# Air858.net
KiCad netlist of a schematic drawn in EAGLE
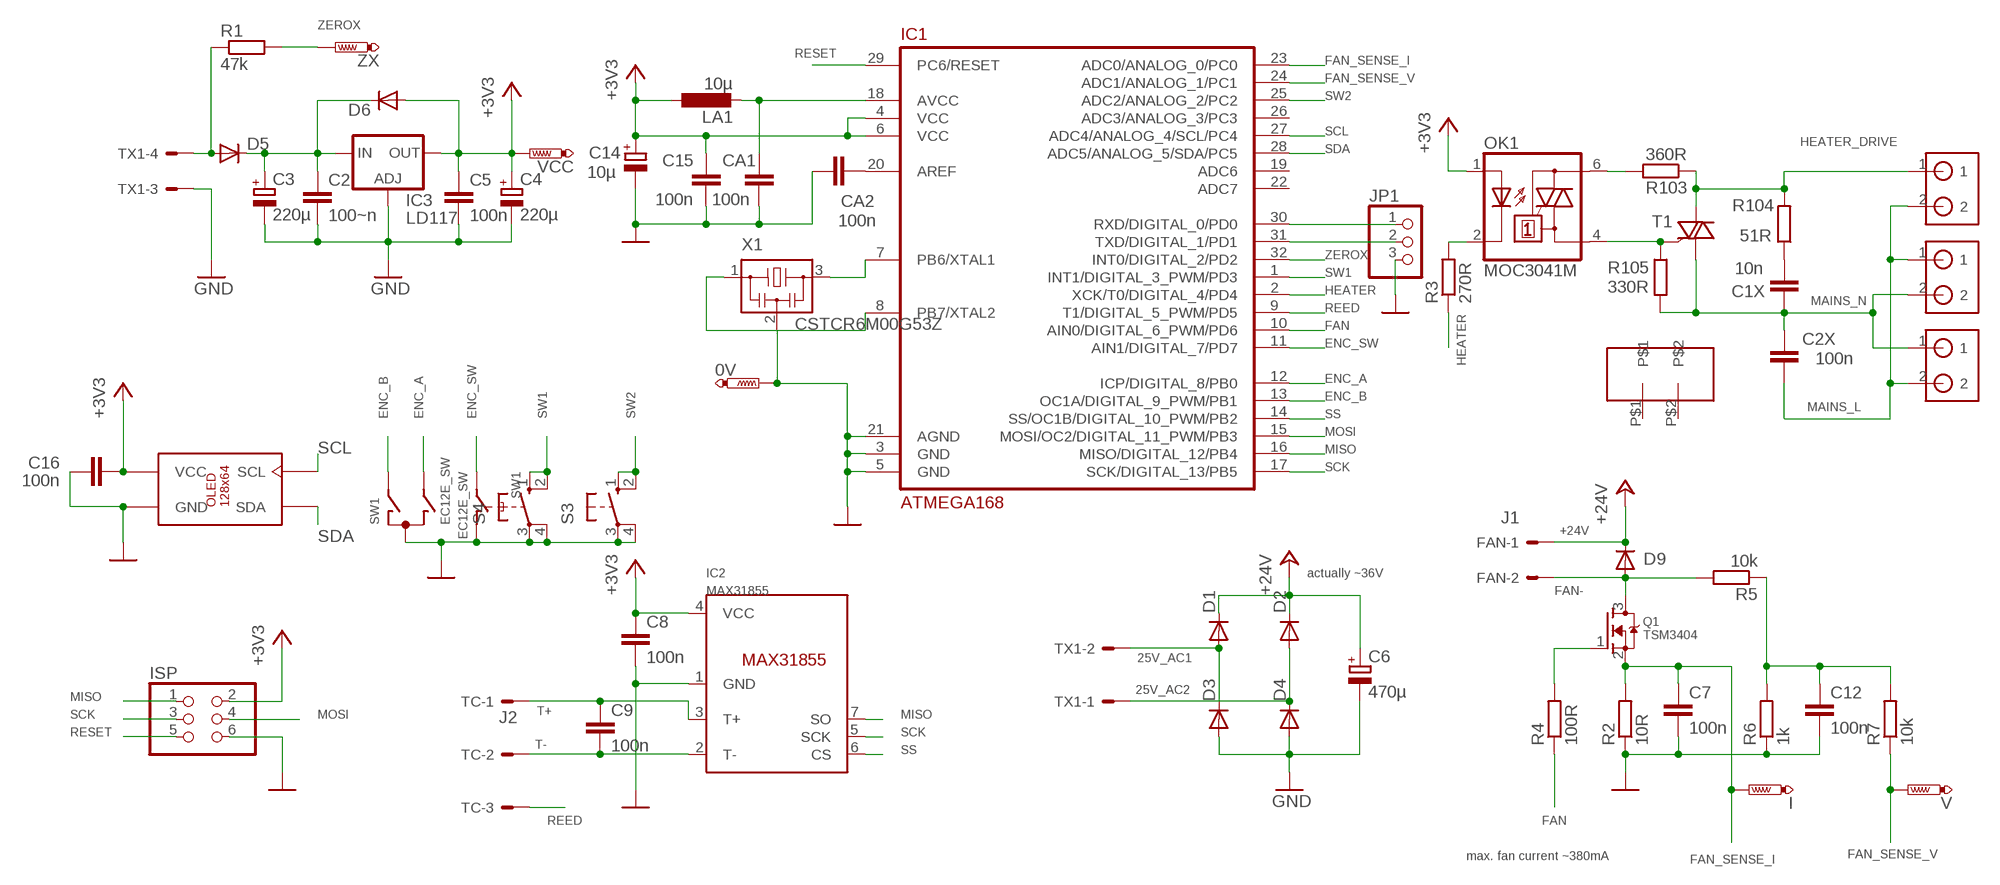
[diagram p0: schematic, sheet 1]

(export (version "E")
  (design (tool "Eeschema 10.0.6"))
  (components
    (comp (ref "0V")
      (value "PTR1B1,27")
      (footprint "eagle-import:B1,27")
      (libsource (lib "eagle-import") (part "PTR1B1,27"))
    )
    (comp (ref "C1X")
      (value "10n")
      (footprint "eagle-import:C075-032X103")
      (libsource (lib "eagle-import") (part "C-EU075-032X103"))
    )
    (comp (ref "C2")
      (value "100~n")
      (footprint "eagle-import:C0603")
      (libsource (lib "eagle-import") (part "C-EUC0603"))
    )
    (comp (ref "C2X")
      (value "100n")
      (footprint "eagle-import:C150-054X183")
      (libsource (lib "eagle-import") (part "C-EU150-054X183"))
    )
    (comp (ref "C3")
      (value "220µ")
      (footprint "eagle-import:SMC_E")
      (libsource (lib "eagle-import") (part "CPOL-EUSMCE"))
    )
    (comp (ref "C4")
      (value "220µ")
      (footprint "eagle-import:SMC_E")
      (libsource (lib "eagle-import") (part "CPOL-EUSMCE"))
    )
    (comp (ref "C5")
      (value "100n")
      (footprint "eagle-import:C0603")
      (libsource (lib "eagle-import") (part "C-EUC0603"))
    )
    (comp (ref "C6")
      (value "470µ")
      (footprint "eagle-import:E5-10,5")
      (libsource (lib "eagle-import") (part "CPOL-EUE5-10.5"))
    )
    (comp (ref "C7")
      (value "100n")
      (footprint "eagle-import:C0603K")
      (libsource (lib "eagle-import") (part "C-EUC0603K"))
    )
    (comp (ref "C8")
      (value "100n")
      (footprint "eagle-import:C0603K")
      (libsource (lib "eagle-import") (part "C-EUC0603K"))
    )
    (comp (ref "C9")
      (value "100n")
      (footprint "eagle-import:C0603K")
      (libsource (lib "eagle-import") (part "C-EUC0603K"))
    )
    (comp (ref "C12")
      (value "100n")
      (footprint "eagle-import:C0603K")
      (libsource (lib "eagle-import") (part "C-EUC0603K"))
    )
    (comp (ref "C14")
      (value "10µ")
      (footprint "eagle-import:B_3528-21W")
      (libsource (lib "eagle-import") (part "CPOL-EUB/3528-21W"))
    )
    (comp (ref "C15")
      (value "100n")
      (footprint "eagle-import:C0603K")
      (libsource (lib "eagle-import") (part "C-EUC0603K"))
    )
    (comp (ref "C16")
      (value "100n")
      (footprint "eagle-import:C0603K")
      (libsource (lib "eagle-import") (part "C-EUC0603K"))
    )
    (comp (ref "CA1")
      (value "100n")
      (footprint "eagle-import:C0603K")
      (libsource (lib "eagle-import") (part "C-EUC0603K"))
    )
    (comp (ref "CA2")
      (value "100n")
      (footprint "eagle-import:C0603K")
      (libsource (lib "eagle-import") (part "C-EUC0603K"))
    )
    (comp (ref "D1")
      (value "DIODE-DO-214AC")
      (footprint "eagle-import:DO-214AC")
      (libsource (lib "eagle-import") (part "DIODE-DO-214AC"))
    )
    (comp (ref "D2")
      (value "DIODE-DO-214AC")
      (footprint "eagle-import:DO-214AC")
      (libsource (lib "eagle-import") (part "DIODE-DO-214AC"))
    )
    (comp (ref "D3")
      (value "DIODE-DO-214AC")
      (footprint "eagle-import:DO-214AC")
      (libsource (lib "eagle-import") (part "DIODE-DO-214AC"))
    )
    (comp (ref "D4")
      (value "DIODE-DO-214AC")
      (footprint "eagle-import:DO-214AC")
      (libsource (lib "eagle-import") (part "DIODE-DO-214AC"))
    )
    (comp (ref "D5")
      (value "DIODE-DO-214AC")
      (footprint "eagle-import:DO-214AC")
      (libsource (lib "eagle-import") (part "DIODE-DO-214AC"))
    )
    (comp (ref "D6")
      (value "DIODE-DO-214AC")
      (footprint "eagle-import:DO-214AC")
      (libsource (lib "eagle-import") (part "DIODE-DO-214AC"))
    )
    (comp (ref "D9")
      (value "DIODE-DO-214AC")
      (footprint "eagle-import:DO-214AC")
      (libsource (lib "eagle-import") (part "DIODE-DO-214AC"))
    )
    (comp (ref "FAN")
      (value "J1")
      (footprint "eagle-import:22-23-2021")
      (fields (field (name "MF") "MOLEX") (field (name "MPN") "22-23-2021"))
      (libsource (lib "eagle-import") (part "22-23-2021"))
    )
    (comp (ref "HEATER")
      (value "2POL5MM")
      (footprint "eagle-import:2POL5MM")
      (libsource (lib "eagle-import") (part "2POL5MM"))
    )
    (comp (ref "I")
      (value "PTR1B1,27")
      (footprint "eagle-import:B1,27")
      (libsource (lib "eagle-import") (part "PTR1B1,27"))
    )
    (comp (ref "IC1")
      (value "ATMEGA168")
      (footprint "eagle-import:QFP32")
      (libsource (lib "eagle-import") (part "AVR-ATMEGA168-TQP32"))
    )
    (comp (ref "IC2")
      (value "MAX31855")
      (footprint "eagle-import:SOIC8")
      (libsource (lib "eagle-import") (part "MAX31855"))
    )
    (comp (ref "IC3")
      (value "LD117")
      (footprint "eagle-import:SOT223")
      (libsource (lib "eagle-import") (part "LD117A?S12TR"))
    )
    (comp (ref "ISP")
      (value "PINHD-2X3")
      (footprint "eagle-import:2X03")
      (libsource (lib "eagle-import") (part "PINHD-2X3"))
    )
    (comp (ref "JP1")
      (value "PINHD-1X3")
      (footprint "eagle-import:1X03")
      (libsource (lib "eagle-import") (part "PINHD-1X3"))
    )
    (comp (ref "LA1")
      (value "10µ")
      (footprint "eagle-import:L3225P")
      (libsource (lib "eagle-import") (part "L-EUL3225P"))
    )
    (comp (ref "MAINS1")
      (value "2POL5MM")
      (footprint "eagle-import:2POL5MM")
      (libsource (lib "eagle-import") (part "2POL5MM"))
    )
    (comp (ref "MAINS2")
      (value "2POL5MM")
      (footprint "eagle-import:2POL5MM")
      (libsource (lib "eagle-import") (part "2POL5MM"))
    )
    (comp (ref "OK1")
      (value "MOC3041M")
      (footprint "eagle-import:DIL06")
      (fields (field (name "MF") "FAIRCHILD SEMICONDUCTOR"))
      (libsource (lib "eagle-import") (part "MOC3041M"))
    )
    (comp (ref "OLED1")
      (value "SSD1306-IIC")
      (footprint "eagle-import:SSD1306-IIC")
      (libsource (lib "eagle-import") (part "SSD1306-IIC"))
    )
    (comp (ref "Q1")
      (value "TSM3404")
      (footprint "eagle-import:SOT23")
      (libsource (lib "eagle-import") (part "MOSFET-NREFLOW"))
    )
    (comp (ref "R1")
      (value "47k")
      (footprint "eagle-import:R0603")
      (libsource (lib "eagle-import") (part "R-EU_R0603"))
    )
    (comp (ref "R2")
      (value "10R")
      (footprint "eagle-import:M1206")
      (libsource (lib "eagle-import") (part "R-EU_M1206"))
    )
    (comp (ref "R3")
      (value "270R")
      (footprint "eagle-import:R0603")
      (libsource (lib "eagle-import") (part "R-EU_R0603"))
    )
    (comp (ref "R4")
      (value "100R")
      (footprint "eagle-import:R0603")
      (libsource (lib "eagle-import") (part "R-EU_R0603"))
    )
    (comp (ref "R5")
      (value "10k")
      (footprint "eagle-import:R0603")
      (libsource (lib "eagle-import") (part "R-EU_R0603"))
    )
    (comp (ref "R6")
      (value "1k")
      (footprint "eagle-import:R0603")
      (libsource (lib "eagle-import") (part "R-EU_R0603"))
    )
    (comp (ref "R7")
      (value "10k")
      (footprint "eagle-import:R0603")
      (libsource (lib "eagle-import") (part "R-EU_R0603"))
    )
    (comp (ref "R103")
      (value "360R")
      (footprint "eagle-import:M1206")
      (libsource (lib "eagle-import") (part "R-EU_M1206"))
    )
    (comp (ref "R104")
      (value "51R")
      (footprint "eagle-import:0309_10")
      (libsource (lib "eagle-import") (part "R-EU_0309/10"))
    )
    (comp (ref "R105")
      (value "330R")
      (footprint "eagle-import:M1206")
      (libsource (lib "eagle-import") (part "R-EU_M1206"))
    )
    (comp (ref "S3")
      (value "40-XX")
      (footprint "eagle-import:B3F-40XX")
      (fields (field (name "MF") "OMRON COMPONENTS USA") (field (name "MPN") "B3F-4000"))
      (libsource (lib "eagle-import") (part "40-XX"))
    )
    (comp (ref "S4")
      (value "40-XX")
      (footprint "eagle-import:B3F-40XX")
      (fields (field (name "MF") "OMRON COMPONENTS USA") (field (name "MPN") "B3F-4000"))
      (libsource (lib "eagle-import") (part "40-XX"))
    )
    (comp (ref "SW1")
      (value "EC12E_SW")
      (footprint "eagle-import:ALPS_EC12E_SW")
      (fields (field (name "MPN") "EC12E2424407"))
      (libsource (lib "eagle-import") (part "EC12E_SW"))
    )
    (comp (ref "T1")
      (value "BTA16")
      (footprint "eagle-import:TO220BV")
      (libsource (lib "eagle-import") (part "TIC206D"))
    )
    (comp (ref "TC")
      (value "J2")
      (footprint "eagle-import:22-23-2031")
      (fields (field (name "MF") "MOLEX") (field (name "MPN") "22-23-2031"))
      (libsource (lib "eagle-import") (part "22-23-2031"))
    )
    (comp (ref "TX1")
      (value "J4")
      (footprint "eagle-import:22-23-2041")
      (fields (field (name "MF") "MOLEX") (field (name "MPN") "22-23-2041"))
      (libsource (lib "eagle-import") (part "22-23-2041"))
    )
    (comp (ref "U$5")
      (value "HEATSINK17X7.5TO220")
      (footprint "eagle-import:HEATSINK17X7.5TO220")
      (libsource (lib "eagle-import") (part "HEATSINK17X7.5TO220"))
    )
    (comp (ref "V")
      (value "PTR1B1,27")
      (footprint "eagle-import:B1,27")
      (libsource (lib "eagle-import") (part "PTR1B1,27"))
    )
    (comp (ref "VCC")
      (value "PTR1B1,27")
      (footprint "eagle-import:B1,27")
      (libsource (lib "eagle-import") (part "PTR1B1,27"))
    )
    (comp (ref "X1")
      (value "CSTCR6M00G53Z")
      (footprint "eagle-import:CSTCR6M")
      (fields (field (name "MPN") "CSTCR6M00G53-R0"))
      (libsource (lib "eagle-import") (part "CSTCR6M00G53Z"))
    )
    (comp (ref "ZX")
      (value "PTR1B1,27")
      (footprint "eagle-import:B1,27")
      (libsource (lib "eagle-import") (part "PTR1B1,27"))
    )
  )
  (nets
    (net (code "1") (name "+3V3") (class "Default")
      (node (ref "C14") (pin "+") (pinfunction "+_+") (pintype "passive"))
      (node (ref "C15") (pin "1") (pinfunction "1_1") (pintype "passive"))
      (node (ref "C16") (pin "2") (pinfunction "2_2") (pintype "passive"))
      (node (ref "C4") (pin "+") (pinfunction "+_+") (pintype "passive"))
      (node (ref "C5") (pin "1") (pinfunction "1_1") (pintype "passive"))
      (node (ref "C8") (pin "1") (pinfunction "1_1") (pintype "passive"))
      (node (ref "D6") (pin "A") (pinfunction "A_A") (pintype "passive"))
      (node (ref "IC1") (pin "4") (pinfunction "VCC_4") (pintype "power_in"))
      (node (ref "IC1") (pin "6") (pinfunction "VCC_6") (pintype "power_in"))
      (node (ref "IC2") (pin "4") (pinfunction "VCC_4") (pintype "power_in"))
      (node (ref "IC3") (pin "4") (pinfunction "OUT_4") (pintype "passive"))
      (node (ref "ISP") (pin "2") (pinfunction "2_2") (pintype "passive"))
      (node (ref "LA1") (pin "1") (pinfunction "1_1") (pintype "passive"))
      (node (ref "OK1") (pin "1") (pinfunction "A_1") (pintype "passive"))
      (node (ref "OLED1") (pin "VCC") (pinfunction "VCC_VCC") (pintype "power_in"))
      (node (ref "VCC") (pin "TP") (pinfunction "TP_TP") (pintype "input"))
    )
    (net (code "2") (name "+24V") (class "Default")
      (node (ref "C6") (pin "+") (pinfunction "+_+") (pintype "passive"))
      (node (ref "D1") (pin "C") (pinfunction "C_C") (pintype "passive"))
      (node (ref "D2") (pin "C") (pinfunction "C_C") (pintype "passive"))
      (node (ref "D9") (pin "C") (pinfunction "C_C") (pintype "passive"))
      (node (ref "FAN") (pin "1") (pinfunction "S_1") (pintype "passive"))
    )
    (net (code "3") (name "/25V_AC1") (class "Default")
      (node (ref "D1") (pin "A") (pinfunction "A_A") (pintype "passive"))
      (node (ref "D3") (pin "C") (pinfunction "C_C") (pintype "passive"))
      (node (ref "TX1") (pin "2") (pinfunction "S_2") (pintype "passive"))
    )
    (net (code "4") (name "/25V_AC2") (class "Default")
      (node (ref "D2") (pin "A") (pinfunction "A_A") (pintype "passive"))
      (node (ref "D4") (pin "C") (pinfunction "C_C") (pintype "passive"))
      (node (ref "TX1") (pin "1") (pinfunction "S_1") (pintype "passive"))
    )
    (net (code "5") (name "/ENC_A") (class "Default")
      (node (ref "IC1") (pin "12") (pinfunction "ICP/DIGITAL_8/PB0_12") (pintype "bidirectional"))
      (node (ref "SW1") (pin "B") (pinfunction "B_B") (pintype "passive"))
    )
    (net (code "6") (name "/ENC_B") (class "Default")
      (node (ref "IC1") (pin "13") (pinfunction "OC1A/DIGITAL_9_PWM/PB1_13") (pintype "bidirectional"))
      (node (ref "SW1") (pin "A") (pinfunction "A_A") (pintype "passive"))
    )
    (net (code "7") (name "/ENC_SW") (class "Default")
      (node (ref "IC1") (pin "11") (pinfunction "AIN1/DIGITAL_7/PD7_11") (pintype "bidirectional"))
      (node (ref "SW1") (pin "E") (pinfunction "2_E") (pintype "passive"))
    )
    (net (code "8") (name "/FAN") (class "Default")
      (node (ref "IC1") (pin "10") (pinfunction "AIN0/DIGITAL_6_PWM/PD6_10") (pintype "bidirectional"))
      (node (ref "R4") (pin "1") (pinfunction "1_1") (pintype "passive"))
    )
    (net (code "9") (name "/FAN-") (class "Default")
      (node (ref "D9") (pin "A") (pinfunction "A_A") (pintype "passive"))
      (node (ref "FAN") (pin "2") (pinfunction "S_2") (pintype "passive"))
      (node (ref "Q1") (pin "3") (pinfunction "D_3") (pintype "bidirectional"))
      (node (ref "R5") (pin "2") (pinfunction "2_2") (pintype "passive"))
    )
    (net (code "10") (name "/FAN_SENSE_I") (class "Default")
      (node (ref "C7") (pin "1") (pinfunction "1_1") (pintype "passive"))
      (node (ref "I") (pin "TP") (pinfunction "TP_TP") (pintype "input"))
      (node (ref "IC1") (pin "23") (pinfunction "ADC0/ANALOG_0/PC0_23") (pintype "bidirectional"))
      (node (ref "Q1") (pin "2") (pinfunction "S_2") (pintype "bidirectional"))
      (node (ref "R2") (pin "2") (pinfunction "2_2") (pintype "passive"))
    )
    (net (code "11") (name "/FAN_SENSE_V") (class "Default")
      (node (ref "IC1") (pin "24") (pinfunction "ADC1/ANALOG_1/PC1_24") (pintype "bidirectional"))
      (node (ref "R7") (pin "1") (pinfunction "1_1") (pintype "passive"))
      (node (ref "V") (pin "TP") (pinfunction "TP_TP") (pintype "input"))
    )
    (net (code "12") (name "/HEATER") (class "Default")
      (node (ref "IC1") (pin "2") (pinfunction "XCK/T0/DIGITAL_4/PD4_2") (pintype "bidirectional"))
      (node (ref "R3") (pin "1") (pinfunction "1_1") (pintype "passive"))
    )
    (net (code "13") (name "/HEATER_DRIVE") (class "Default")
      (node (ref "HEATER") (pin "1") (pinfunction "1_1") (pintype "bidirectional"))
      (node (ref "R103") (pin "1") (pinfunction "1_1") (pintype "passive"))
      (node (ref "R104") (pin "2") (pinfunction "2_2") (pintype "passive"))
      (node (ref "T1") (pin "T2") (pinfunction "A2_T2") (pintype "passive"))
    )
    (net (code "14") (name "/MAINS_L") (class "Default")
      (node (ref "C2X") (pin "1") (pinfunction "1_1") (pintype "passive"))
      (node (ref "HEATER") (pin "2") (pinfunction "2_2") (pintype "bidirectional"))
      (node (ref "MAINS1") (pin "1") (pinfunction "1_1") (pintype "bidirectional"))
      (node (ref "MAINS2") (pin "2") (pinfunction "2_2") (pintype "bidirectional"))
    )
    (net (code "15") (name "/MAINS_N") (class "Default")
      (node (ref "C1X") (pin "1") (pinfunction "1_1") (pintype "passive"))
      (node (ref "C2X") (pin "2") (pinfunction "2_2") (pintype "passive"))
      (node (ref "MAINS1") (pin "2") (pinfunction "2_2") (pintype "bidirectional"))
      (node (ref "MAINS2") (pin "1") (pinfunction "1_1") (pintype "bidirectional"))
      (node (ref "R105") (pin "2") (pinfunction "2_2") (pintype "passive"))
      (node (ref "T1") (pin "T1") (pinfunction "A1_T1") (pintype "passive"))
    )
    (net (code "16") (name "/MISO") (class "Default")
      (node (ref "IC1") (pin "16") (pinfunction "MISO/DIGITAL_12/PB4_16") (pintype "bidirectional"))
      (node (ref "IC2") (pin "7") (pinfunction "SO_7") (pintype "output"))
      (node (ref "ISP") (pin "1") (pinfunction "1_1") (pintype "passive"))
    )
    (net (code "17") (name "/MOSI") (class "Default")
      (node (ref "IC1") (pin "15") (pinfunction "MOSI/OC2/DIGITAL_11_PWM/PB3_15") (pintype "bidirectional"))
      (node (ref "ISP") (pin "4") (pinfunction "4_4") (pintype "passive"))
    )
    (net (code "18") (name "/REED") (class "Default")
      (node (ref "IC1") (pin "9") (pinfunction "T1/DIGITAL_5_PWM/PD5_9") (pintype "bidirectional"))
      (node (ref "TC") (pin "3") (pinfunction "S_3") (pintype "passive"))
    )
    (net (code "19") (name "/RESET") (class "Default")
      (node (ref "IC1") (pin "29") (pinfunction "PC6/RESET_29") (pintype "bidirectional"))
      (node (ref "ISP") (pin "5") (pinfunction "5_5") (pintype "passive"))
    )
    (net (code "20") (name "/SCK") (class "Default")
      (node (ref "IC1") (pin "17") (pinfunction "SCK/DIGITAL_13/PB5_17") (pintype "bidirectional"))
      (node (ref "IC2") (pin "5") (pinfunction "SCK_5") (pintype "input"))
      (node (ref "ISP") (pin "3") (pinfunction "3_3") (pintype "passive"))
    )
    (net (code "21") (name "/SCL") (class "Default")
      (node (ref "IC1") (pin "27") (pinfunction "ADC4/ANALOG_4/SCL/PC4_27") (pintype "bidirectional"))
      (node (ref "OLED1") (pin "SCL") (pinfunction "SCL_SCL") (pintype "bidirectional"))
    )
    (net (code "22") (name "/SDA") (class "Default")
      (node (ref "IC1") (pin "28") (pinfunction "ADC5/ANALOG_5/SDA/PC5_28") (pintype "bidirectional"))
      (node (ref "OLED1") (pin "SDA") (pinfunction "SDA_SDA") (pintype "bidirectional"))
    )
    (net (code "23") (name "/SS") (class "Default")
      (node (ref "IC1") (pin "14") (pinfunction "SS/OC1B/DIGITAL_10_PWM/PB2_14") (pintype "bidirectional"))
      (node (ref "IC2") (pin "6") (pinfunction "CS_6") (pintype "input"))
    )
    (net (code "24") (name "/SW1") (class "Default")
      (node (ref "IC1") (pin "1") (pinfunction "INT1/DIGITAL_3_PWM/PD3_1") (pintype "bidirectional"))
      (node (ref "S4") (pin "1") (pinfunction "S_1") (pintype "passive"))
      (node (ref "S4") (pin "2") (pinfunction "S1_2") (pintype "passive"))
    )
    (net (code "25") (name "/SW2") (class "Default")
      (node (ref "IC1") (pin "25") (pinfunction "ADC2/ANALOG_2/PC2_25") (pintype "bidirectional"))
      (node (ref "S3") (pin "1") (pinfunction "S_1") (pintype "passive"))
      (node (ref "S3") (pin "2") (pinfunction "S1_2") (pintype "passive"))
    )
    (net (code "26") (name "/T+") (class "Default")
      (node (ref "C9") (pin "1") (pinfunction "1_1") (pintype "passive"))
      (node (ref "IC2") (pin "3") (pinfunction "T+_3") (pintype "input"))
      (node (ref "TC") (pin "1") (pinfunction "S_1") (pintype "passive"))
    )
    (net (code "27") (name "/T-") (class "Default")
      (node (ref "C9") (pin "2") (pinfunction "2_2") (pintype "passive"))
      (node (ref "IC2") (pin "2") (pinfunction "T-_2") (pintype "input"))
      (node (ref "TC") (pin "2") (pinfunction "S_2") (pintype "passive"))
    )
    (net (code "28") (name "/ZEROX") (class "Default")
      (node (ref "IC1") (pin "32") (pinfunction "INT0/DIGITAL_2/PD2_32") (pintype "bidirectional"))
      (node (ref "R1") (pin "2") (pinfunction "2_2") (pintype "passive"))
      (node (ref "ZX") (pin "TP") (pinfunction "TP_TP") (pintype "input"))
    )
    (net (code "29") (name "GND") (class "Default")
      (node (ref "0V") (pin "TP") (pinfunction "TP_TP") (pintype "input"))
      (node (ref "C12") (pin "2") (pinfunction "2_2") (pintype "passive"))
      (node (ref "C14") (pin "-") (pinfunction "-_-") (pintype "passive"))
      (node (ref "C15") (pin "2") (pinfunction "2_2") (pintype "passive"))
      (node (ref "C16") (pin "1") (pinfunction "1_1") (pintype "passive"))
      (node (ref "C2") (pin "2") (pinfunction "2_2") (pintype "passive"))
      (node (ref "C3") (pin "-") (pinfunction "-_-") (pintype "passive"))
      (node (ref "C4") (pin "-") (pinfunction "-_-") (pintype "passive"))
      (node (ref "C5") (pin "2") (pinfunction "2_2") (pintype "passive"))
      (node (ref "C6") (pin "-") (pinfunction "-_-") (pintype "passive"))
      (node (ref "C7") (pin "2") (pinfunction "2_2") (pintype "passive"))
      (node (ref "C8") (pin "2") (pinfunction "2_2") (pintype "passive"))
      (node (ref "CA1") (pin "2") (pinfunction "2_2") (pintype "passive"))
      (node (ref "CA2") (pin "1") (pinfunction "1_1") (pintype "passive"))
      (node (ref "D3") (pin "A") (pinfunction "A_A") (pintype "passive"))
      (node (ref "D4") (pin "A") (pinfunction "A_A") (pintype "passive"))
      (node (ref "IC1") (pin "21") (pinfunction "AGND_21") (pintype "power_in"))
      (node (ref "IC1") (pin "3") (pinfunction "GND_3") (pintype "power_in"))
      (node (ref "IC1") (pin "5") (pinfunction "GND_5") (pintype "power_in"))
      (node (ref "IC2") (pin "1") (pinfunction "GND_1") (pintype "power_in"))
      (node (ref "IC3") (pin "1") (pinfunction "ADJ_1") (pintype "input"))
      (node (ref "ISP") (pin "6") (pinfunction "6_6") (pintype "passive"))
      (node (ref "JP1") (pin "3") (pinfunction "3_3") (pintype "passive"))
      (node (ref "OLED1") (pin "GND") (pinfunction "GND_GND") (pintype "power_in"))
      (node (ref "R2") (pin "1") (pinfunction "1_1") (pintype "passive"))
      (node (ref "R6") (pin "1") (pinfunction "1_1") (pintype "passive"))
      (node (ref "S3") (pin "3") (pinfunction "P_3") (pintype "passive"))
      (node (ref "S3") (pin "4") (pinfunction "P1_4") (pintype "passive"))
      (node (ref "S4") (pin "3") (pinfunction "P_3") (pintype "passive"))
      (node (ref "S4") (pin "4") (pinfunction "P1_4") (pintype "passive"))
      (node (ref "SW1") (pin "C") (pinfunction "C_C") (pintype "passive"))
      (node (ref "SW1") (pin "D") (pinfunction "1_D") (pintype "passive"))
      (node (ref "TX1") (pin "3") (pinfunction "S_3") (pintype "passive"))
      (node (ref "X1") (pin "2") (pinfunction "2_2") (pintype "passive"))
    )
    (net (code "30") (name "Net-(C1X-Pad2)") (class "Default")
      (node (ref "C1X") (pin "2") (pinfunction "2_2") (pintype "passive"))
      (node (ref "R104") (pin "1") (pinfunction "1_1") (pintype "passive"))
    )
    (net (code "31") (name "Net-(C12-Pad1)") (class "Default")
      (node (ref "C12") (pin "1") (pinfunction "1_1") (pintype "passive"))
      (node (ref "R5") (pin "1") (pinfunction "1_1") (pintype "passive"))
      (node (ref "R6") (pin "2") (pinfunction "2_2") (pintype "passive"))
      (node (ref "R7") (pin "2") (pinfunction "2_2") (pintype "passive"))
    )
    (net (code "32") (name "Net-(IC1-AREF)") (class "Default")
      (node (ref "CA2") (pin "2") (pinfunction "2_2") (pintype "passive"))
      (node (ref "IC1") (pin "20") (pinfunction "AREF_20") (pintype "bidirectional"))
    )
    (net (code "33") (name "Net-(IC1-AVCC)") (class "Default")
      (node (ref "CA1") (pin "1") (pinfunction "1_1") (pintype "passive"))
      (node (ref "IC1") (pin "18") (pinfunction "AVCC_18") (pintype "power_in"))
      (node (ref "LA1") (pin "2") (pinfunction "2_2") (pintype "passive"))
    )
    (net (code "34") (name "Net-(IC1-PB6{slash}XTAL1)") (class "Default")
      (node (ref "IC1") (pin "7") (pinfunction "PB6/XTAL1_7") (pintype "bidirectional"))
      (node (ref "X1") (pin "3") (pinfunction "3_3") (pintype "passive"))
    )
    (net (code "35") (name "Net-(IC1-PB7{slash}XTAL2)") (class "Default")
      (node (ref "IC1") (pin "8") (pinfunction "PB7/XTAL2_8") (pintype "bidirectional"))
      (node (ref "X1") (pin "1") (pinfunction "1_1") (pintype "passive"))
    )
    (net (code "36") (name "Net-(IC1-RXD{slash}DIGITAL_0{slash}PD0)") (class "Default")
      (node (ref "IC1") (pin "30") (pinfunction "RXD/DIGITAL_0/PD0_30") (pintype "bidirectional"))
      (node (ref "JP1") (pin "1") (pinfunction "1_1") (pintype "passive"))
    )
    (net (code "37") (name "Net-(IC1-TXD{slash}DIGITAL_1{slash}PD1)") (class "Default")
      (node (ref "IC1") (pin "31") (pinfunction "TXD/DIGITAL_1/PD1_31") (pintype "bidirectional"))
      (node (ref "JP1") (pin "2") (pinfunction "2_2") (pintype "passive"))
    )
    (net (code "38") (name "Net-(IC3-IN)") (class "Default")
      (node (ref "C2") (pin "1") (pinfunction "1_1") (pintype "passive"))
      (node (ref "C3") (pin "+") (pinfunction "+_+") (pintype "passive"))
      (node (ref "D5") (pin "C") (pinfunction "C_C") (pintype "passive"))
      (node (ref "D6") (pin "C") (pinfunction "C_C") (pintype "passive"))
      (node (ref "IC3") (pin "3") (pinfunction "IN_3") (pintype "input"))
    )
    (net (code "39") (name "Net-(OK1-A1)") (class "Default")
      (node (ref "OK1") (pin "4") (pinfunction "A1_4") (pintype "passive"))
      (node (ref "R105") (pin "1") (pinfunction "1_1") (pintype "passive"))
      (node (ref "T1") (pin "G") (pinfunction "G_G") (pintype "passive"))
    )
    (net (code "40") (name "Net-(OK1-A2)") (class "Default")
      (node (ref "OK1") (pin "6") (pinfunction "A2_6") (pintype "passive"))
      (node (ref "R103") (pin "2") (pinfunction "2_2") (pintype "passive"))
    )
    (net (code "41") (name "Net-(OK1-C)") (class "Default")
      (node (ref "OK1") (pin "2") (pinfunction "C_2") (pintype "passive"))
      (node (ref "R3") (pin "2") (pinfunction "2_2") (pintype "passive"))
    )
    (net (code "42") (name "Net-(Q1-G)") (class "Default")
      (node (ref "Q1") (pin "1") (pinfunction "G_1") (pintype "bidirectional"))
      (node (ref "R4") (pin "2") (pinfunction "2_2") (pintype "passive"))
    )
    (net (code "43") (name "Net-(TX1D-S)") (class "Default")
      (node (ref "D5") (pin "A") (pinfunction "A_A") (pintype "passive"))
      (node (ref "R1") (pin "1") (pinfunction "1_1") (pintype "passive"))
      (node (ref "TX1") (pin "4") (pinfunction "S_4") (pintype "passive"))
    )
    (net (code "44") (name "unconnected-(IC1-ADC3{slash}ANALOG_3{slash}PC3-Pad26)") (class "Default")
      (node (ref "IC1") (pin "26") (pinfunction "ADC3/ANALOG_3/PC3_26") (pintype "bidirectional"))
    )
    (net (code "45") (name "unconnected-(IC1-ADC6-Pad19)") (class "Default")
      (node (ref "IC1") (pin "19") (pinfunction "ADC6_19") (pintype "bidirectional"))
    )
    (net (code "46") (name "unconnected-(IC1-ADC7-Pad22)") (class "Default")
      (node (ref "IC1") (pin "22") (pinfunction "ADC7_22") (pintype "bidirectional"))
    )
    (net (code "47") (name "unconnected-(U$5-PadP$1)") (class "Default")
      (node (ref "U$5") (pin "P$1") (pinfunction "P$1_P$1") (pintype "bidirectional"))
    )
    (net (code "48") (name "unconnected-(U$5-PadP$2)") (class "Default")
      (node (ref "U$5") (pin "P$2") (pinfunction "P$2_P$2") (pintype "bidirectional"))
    )
  )
)
